# MainBoard.net
KiCad netlist of a schematic drawn in EAGLE
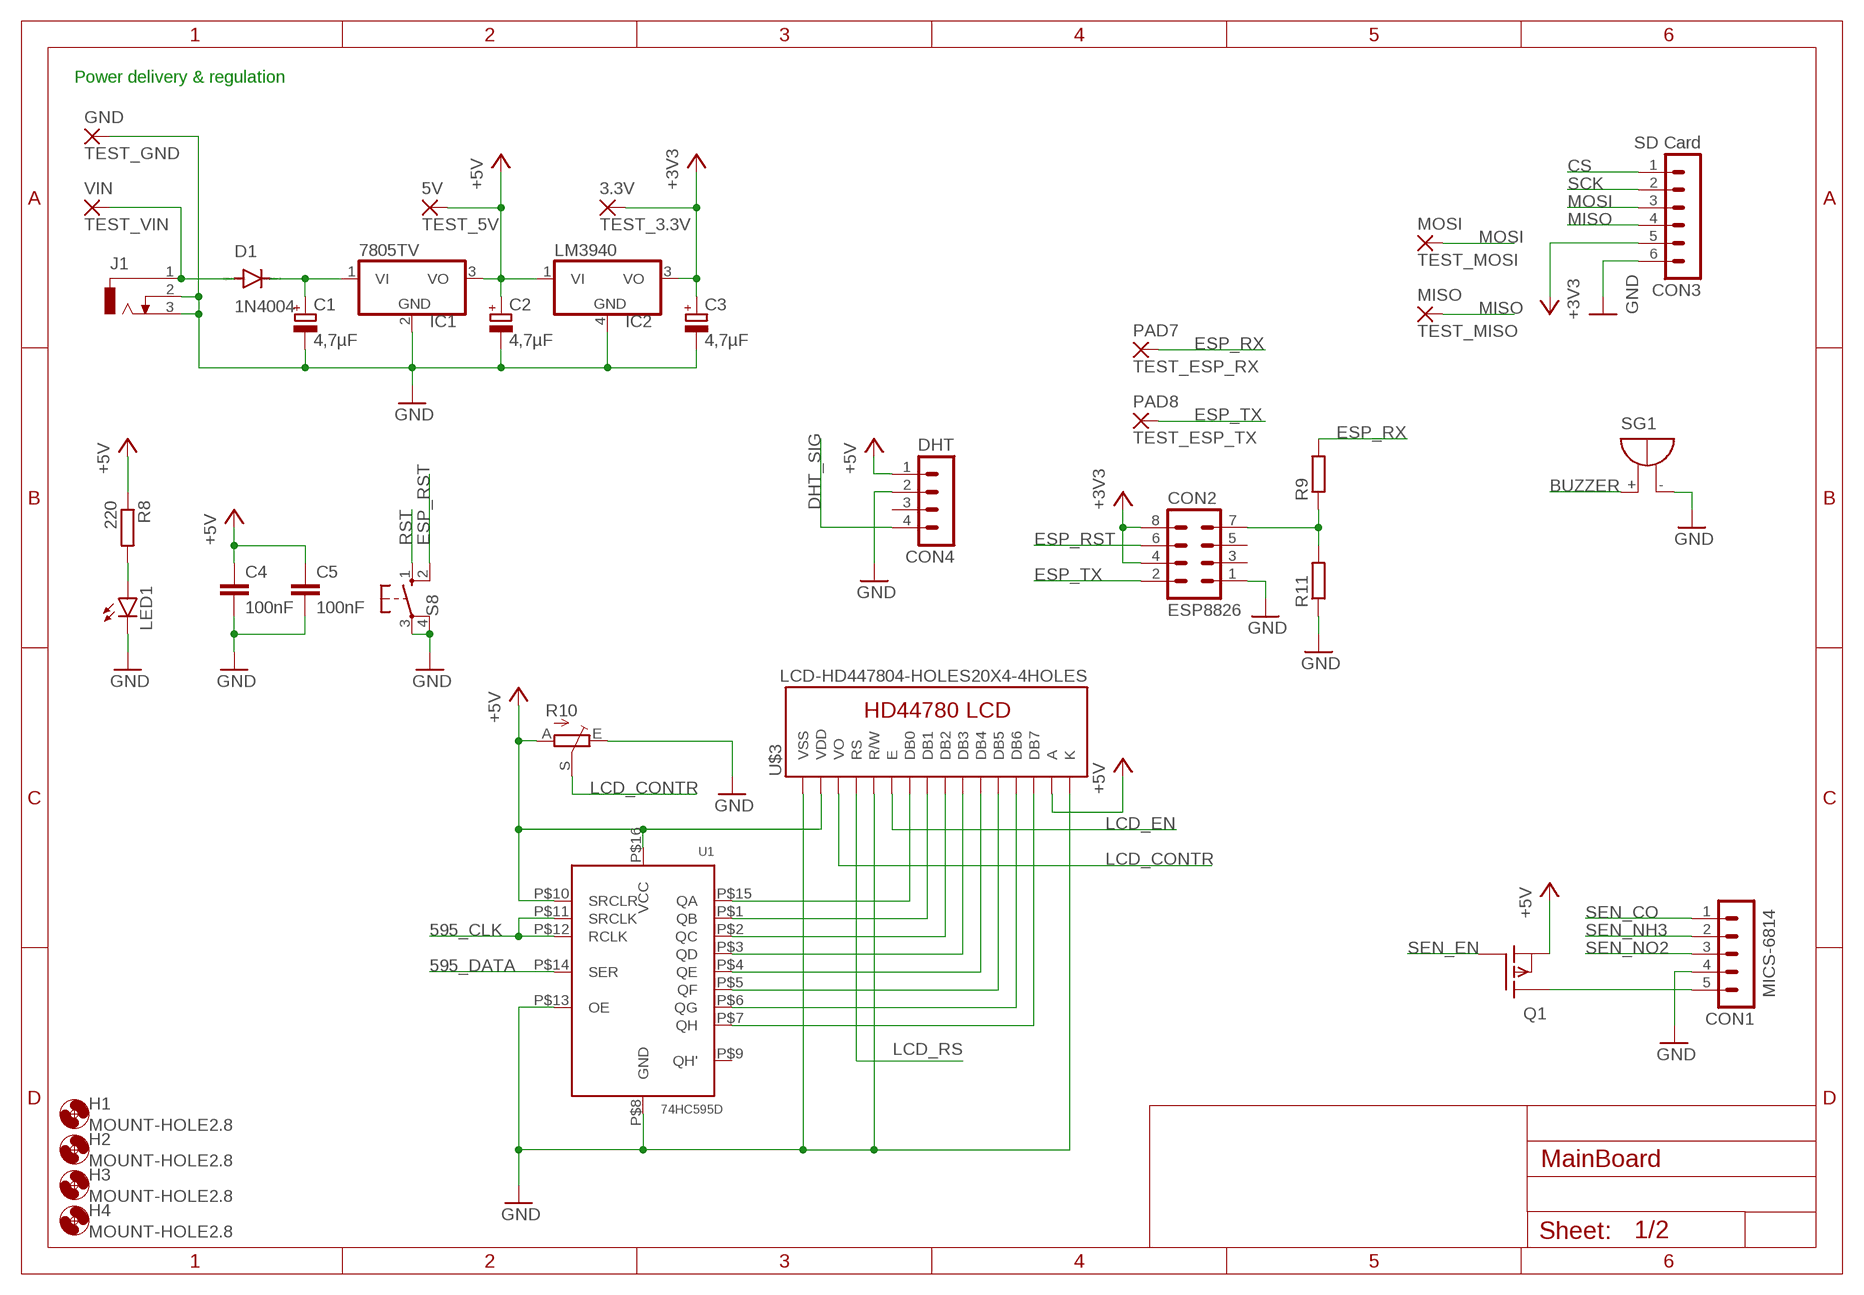
[diagram p0: schematic, sheet 1]
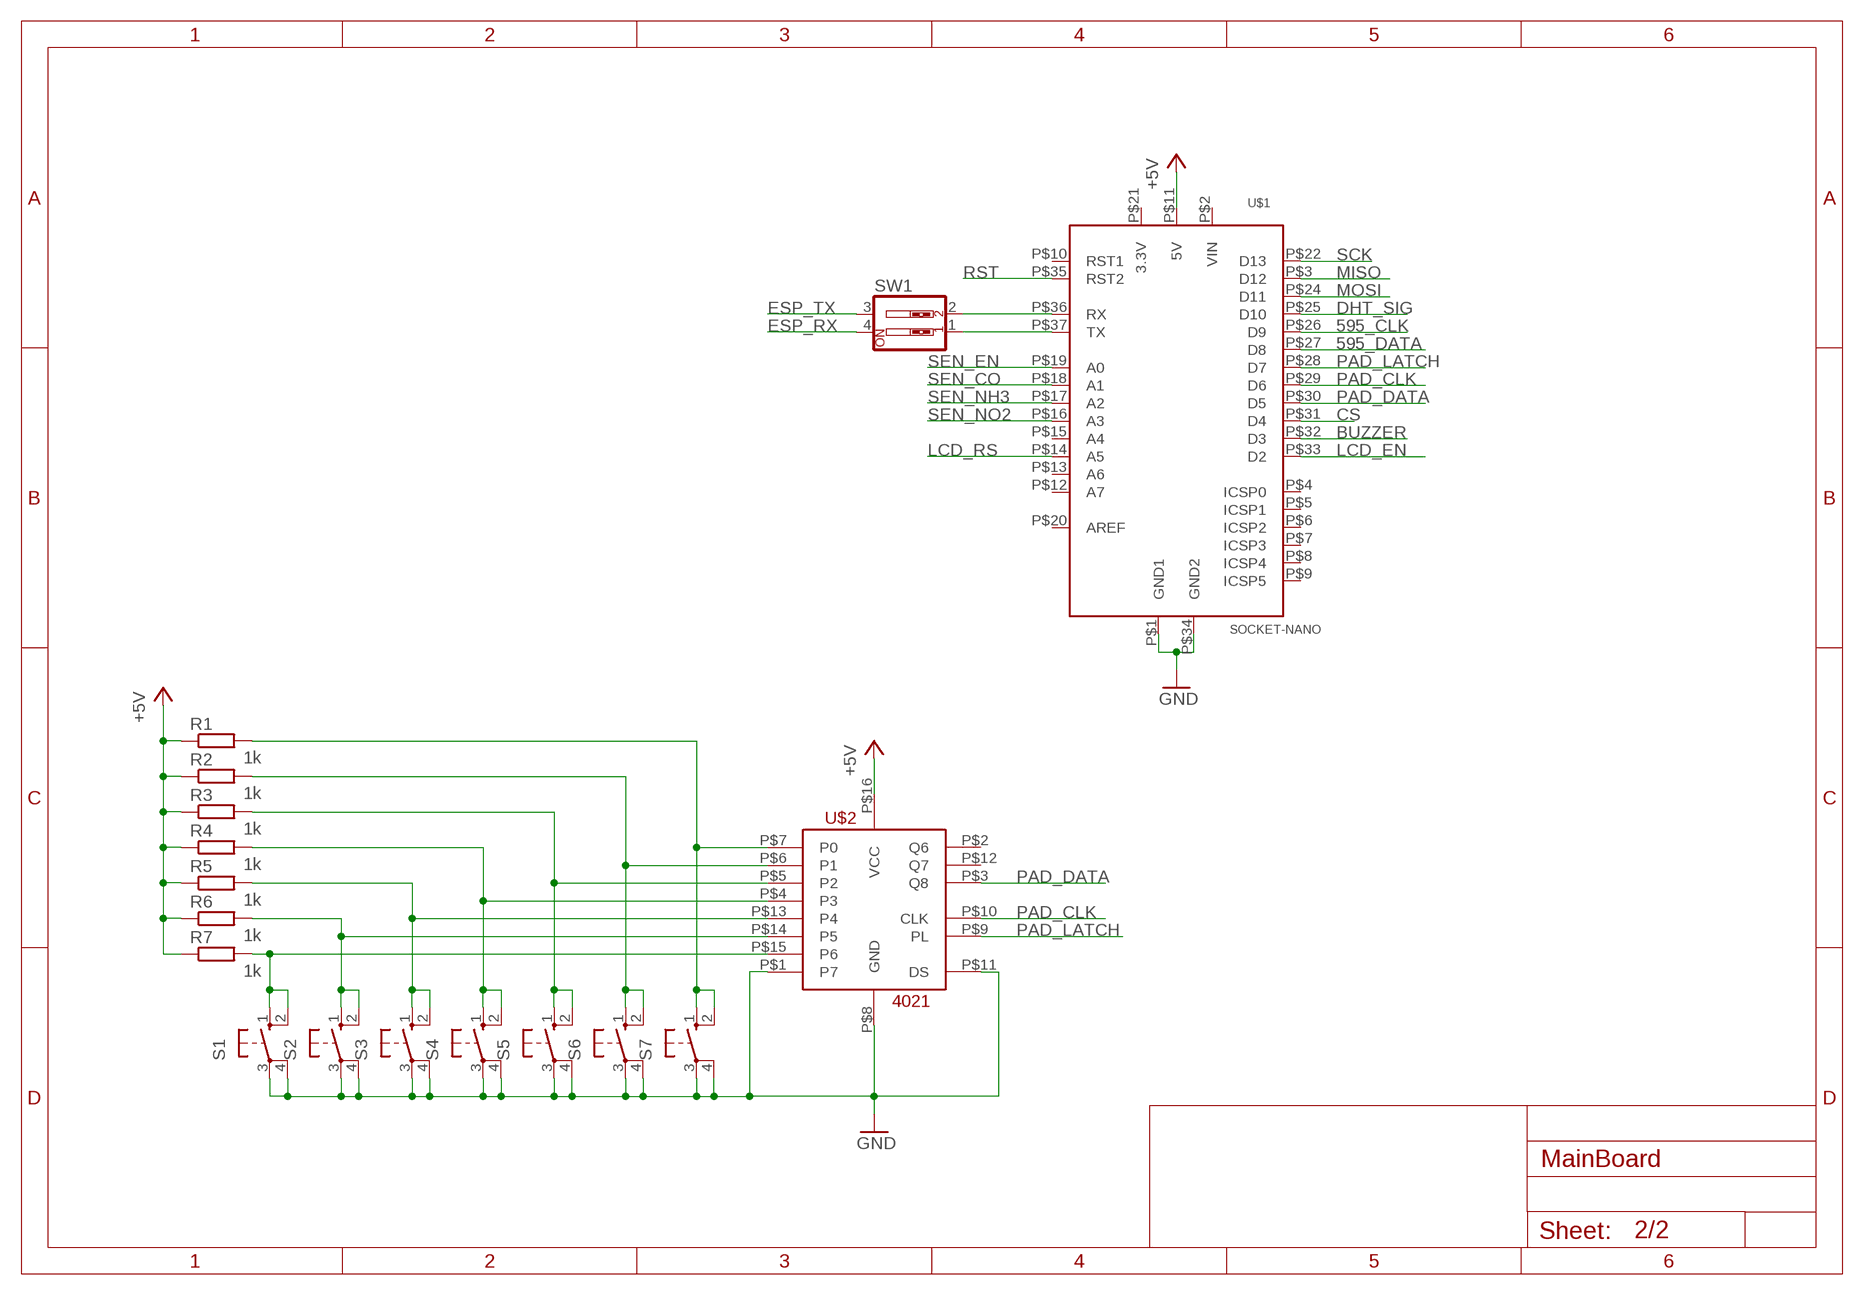
[diagram p1: schematic, sheet 2]

(export (version "E")
  (design (tool "Eeschema 10.0.6"))
  (components
    (comp (ref "3.3V")
      (value "TEST_3.3V")
      (footprint "eagle-import:2,54_0,9")
      (libsource (lib "eagle-import") (part "WIREPAD2,54/0,9"))
    )
    (comp (ref "5V")
      (value "TEST_5V")
      (footprint "eagle-import:2,54_0,9")
      (libsource (lib "eagle-import") (part "WIREPAD2,54/0,9"))
    )
    (comp (ref "C1")
      (value "4,7µF")
      (footprint "eagle-import:E2,5-6E")
      (libsource (lib "eagle-import") (part "CPOL-EUE2,5-6E"))
    )
    (comp (ref "C2")
      (value "4,7µF")
      (footprint "eagle-import:E2,5-6E")
      (libsource (lib "eagle-import") (part "CPOL-EUE2,5-6E"))
    )
    (comp (ref "C3")
      (value "4,7µF")
      (footprint "eagle-import:E2,5-6E")
      (libsource (lib "eagle-import") (part "CPOL-EUE2,5-6E"))
    )
    (comp (ref "C4")
      (value "100nF")
      (footprint "eagle-import:C0805")
      (libsource (lib "eagle-import") (part "C-EUC0805"))
    )
    (comp (ref "C5")
      (value "100nF")
      (footprint "eagle-import:C0805")
      (libsource (lib "eagle-import") (part "C-EUC0805"))
    )
    (comp (ref "CON1")
      (value "MICS-6814")
      (footprint "eagle-import:MA05-1")
      (libsource (lib "eagle-import") (part "MA05-1"))
    )
    (comp (ref "CON2")
      (value "ESP8826")
      (footprint "eagle-import:MA04-2")
      (libsource (lib "eagle-import") (part "MA04-2"))
    )
    (comp (ref "CON3")
      (value "SD Card")
      (footprint "eagle-import:MA06-1")
      (libsource (lib "eagle-import") (part "MA06-1"))
    )
    (comp (ref "CON4")
      (value "DHT")
      (footprint "eagle-import:MA04-1")
      (libsource (lib "eagle-import") (part "MA04-1"))
    )
    (comp (ref "D1")
      (value "1N4004")
      (footprint "eagle-import:DO34-7")
      (libsource (lib "eagle-import") (part "BAS15"))
    )
    (comp (ref "GND")
      (value "TEST_GND")
      (footprint "eagle-import:2,54_0,9")
      (libsource (lib "eagle-import") (part "WIREPAD2,54/0,9"))
    )
    (comp (ref "H1")
      (value "MOUNT-HOLE2.8")
      (footprint "eagle-import:2,8")
      (libsource (lib "eagle-import") (part "MOUNT-HOLE2.8"))
    )
    (comp (ref "H2")
      (value "MOUNT-HOLE2.8")
      (footprint "eagle-import:2,8")
      (libsource (lib "eagle-import") (part "MOUNT-HOLE2.8"))
    )
    (comp (ref "H3")
      (value "MOUNT-HOLE2.8")
      (footprint "eagle-import:2,8")
      (libsource (lib "eagle-import") (part "MOUNT-HOLE2.8"))
    )
    (comp (ref "H4")
      (value "MOUNT-HOLE2.8")
      (footprint "eagle-import:2,8")
      (libsource (lib "eagle-import") (part "MOUNT-HOLE2.8"))
    )
    (comp (ref "IC1")
      (value "7805TV")
      (footprint "eagle-import:TO220V")
      (libsource (lib "eagle-import") (part "78TV05"))
    )
    (comp (ref "IC2")
      (value "LM3940")
      (footprint "eagle-import:SOT223")
      (libsource (lib "eagle-import") (part "LM340?-MP05"))
    )
    (comp (ref "J1")
      (value "DCJ0303")
      (footprint "eagle-import:DCJ0303")
      (libsource (lib "eagle-import") (part "DCJ0303"))
    )
    (comp (ref "LED1")
      (value "LED3MM")
      (footprint "eagle-import:LED3MM")
      (libsource (lib "eagle-import") (part "LED3MM"))
    )
    (comp (ref "MISO")
      (value "TEST_MISO")
      (footprint "eagle-import:2,54_0,9")
      (libsource (lib "eagle-import") (part "WIREPAD2,54/0,9"))
    )
    (comp (ref "MOSI")
      (value "TEST_MOSI")
      (footprint "eagle-import:2,54_0,9")
      (libsource (lib "eagle-import") (part "WIREPAD2,54/0,9"))
    )
    (comp (ref "PAD7")
      (value "TEST_ESP_RX")
      (footprint "eagle-import:2,54_0,9")
      (libsource (lib "eagle-import") (part "WIREPAD2,54/0,9"))
    )
    (comp (ref "PAD8")
      (value "TEST_ESP_TX")
      (footprint "eagle-import:2,54_0,9")
      (libsource (lib "eagle-import") (part "WIREPAD2,54/0,9"))
    )
    (comp (ref "Q1")
      (value "LP0701N3")
      (footprint "eagle-import:TO-92")
      (libsource (lib "eagle-import") (part "LP0701N3"))
    )
    (comp (ref "R8")
      (value "220")
      (footprint "eagle-import:0204_7")
      (libsource (lib "eagle-import") (part "R-EU_0204/7"))
    )
    (comp (ref "R9")
      (value "R-EU_M0805")
      (footprint "eagle-import:M0805")
      (libsource (lib "eagle-import") (part "R-EU_M0805"))
    )
    (comp (ref "R10")
      (value "TRIM_EU-RJ9W")
      (footprint "eagle-import:RJ9W")
      (libsource (lib "eagle-import") (part "TRIM_EU-RJ9W"))
    )
    (comp (ref "R11")
      (value "R-EU_M0805")
      (footprint "eagle-import:M0805")
      (libsource (lib "eagle-import") (part "R-EU_M0805"))
    )
    (comp (ref "S8")
      (value "10-XX")
      (footprint "eagle-import:B3F-10XX")
      (fields (field (name "MPN") "B3F-1000"))
      (libsource (lib "eagle-import") (part "10-XX"))
    )
    (comp (ref "SG1")
      (value "F/TMB")
      (footprint "eagle-import:F_TMB")
      (libsource (lib "eagle-import") (part "F/TMB"))
    )
    (comp (ref "U$3")
      (value "LCD-HD447804-HOLES20X4-4HOLES")
      (footprint "eagle-import:LCD-20X4-4HOLES")
      (libsource (lib "eagle-import") (part "LCD-HD4478020X4-4HOLES4-HOLES"))
    )
    (comp (ref "U1")
      (value "74HC595D")
      (footprint "eagle-import:SOP-16")
      (libsource (lib "eagle-import") (part "74HC595D_SOP16"))
    )
    (comp (ref "VIN")
      (value "TEST_VIN")
      (footprint "eagle-import:2,54_0,9")
      (libsource (lib "eagle-import") (part "WIREPAD2,54/0,9"))
    )
    (comp (ref "R1")
      (value "1k")
      (footprint "eagle-import:0204_7")
      (libsource (lib "eagle-import") (part "R-EU_0204/7"))
    )
    (comp (ref "R2")
      (value "1k")
      (footprint "eagle-import:0204_7")
      (libsource (lib "eagle-import") (part "R-EU_0204/7"))
    )
    (comp (ref "R3")
      (value "1k")
      (footprint "eagle-import:0204_7")
      (libsource (lib "eagle-import") (part "R-EU_0204/7"))
    )
    (comp (ref "R4")
      (value "1k")
      (footprint "eagle-import:0204_7")
      (libsource (lib "eagle-import") (part "R-EU_0204/7"))
    )
    (comp (ref "R5")
      (value "1k")
      (footprint "eagle-import:0204_7")
      (libsource (lib "eagle-import") (part "R-EU_0204/7"))
    )
    (comp (ref "R6")
      (value "1k")
      (footprint "eagle-import:0204_7")
      (libsource (lib "eagle-import") (part "R-EU_0204/7"))
    )
    (comp (ref "R7")
      (value "1k")
      (footprint "eagle-import:0204_7")
      (libsource (lib "eagle-import") (part "R-EU_0204/7"))
    )
    (comp (ref "S1")
      (value "10-XX")
      (footprint "eagle-import:B3F-10XX")
      (fields (field (name "MPN") "B3F-1000"))
      (libsource (lib "eagle-import") (part "10-XX"))
    )
    (comp (ref "S2")
      (value "10-XX")
      (footprint "eagle-import:B3F-10XX")
      (fields (field (name "MPN") "B3F-1000"))
      (libsource (lib "eagle-import") (part "10-XX"))
    )
    (comp (ref "S3")
      (value "10-XX")
      (footprint "eagle-import:B3F-10XX")
      (fields (field (name "MPN") "B3F-1000"))
      (libsource (lib "eagle-import") (part "10-XX"))
    )
    (comp (ref "S4")
      (value "10-XX")
      (footprint "eagle-import:B3F-10XX")
      (fields (field (name "MPN") "B3F-1000"))
      (libsource (lib "eagle-import") (part "10-XX"))
    )
    (comp (ref "S5")
      (value "10-XX")
      (footprint "eagle-import:B3F-10XX")
      (fields (field (name "MPN") "B3F-1000"))
      (libsource (lib "eagle-import") (part "10-XX"))
    )
    (comp (ref "S6")
      (value "10-XX")
      (footprint "eagle-import:B3F-10XX")
      (fields (field (name "MPN") "B3F-1000"))
      (libsource (lib "eagle-import") (part "10-XX"))
    )
    (comp (ref "S7")
      (value "10-XX")
      (footprint "eagle-import:B3F-10XX")
      (fields (field (name "MPN") "B3F-1000"))
      (libsource (lib "eagle-import") (part "10-XX"))
    )
    (comp (ref "SW1")
      (value "SW_DIP-2")
      (footprint "eagle-import:EDG-02")
      (libsource (lib "eagle-import") (part "SW_DIP-2"))
    )
    (comp (ref "U$1")
      (value "SOCKET-NANO")
      (footprint "eagle-import:SOCKET-NANO")
      (libsource (lib "eagle-import") (part "SOCKET-NANO"))
    )
    (comp (ref "U$2")
      (value "4021")
      (footprint "eagle-import:DIP")
      (libsource (lib "eagle-import") (part "4021"))
    )
  )
  (nets
    (net (code "1") (name "+3V3") (class "Default")
      (node (ref "3.3V") (pin "1") (pinfunction "P_1") (pintype "passive"))
      (node (ref "C3") (pin "+") (pinfunction "+_+") (pintype "passive"))
      (node (ref "CON2") (pin "4") (pinfunction "4_4") (pintype "passive"))
      (node (ref "CON2") (pin "8") (pinfunction "8_8") (pintype "passive"))
      (node (ref "CON3") (pin "5") (pinfunction "5_5") (pintype "passive"))
      (node (ref "IC2") (pin "3") (pinfunction "VO_3") (pintype "passive"))
    )
    (net (code "2") (name "+5V") (class "Default")
      (node (ref "5V") (pin "1") (pinfunction "P_1") (pintype "passive"))
      (node (ref "C2") (pin "+") (pinfunction "+_+") (pintype "passive"))
      (node (ref "C4") (pin "1") (pinfunction "1_1") (pintype "passive"))
      (node (ref "C5") (pin "1") (pinfunction "1_1") (pintype "passive"))
      (node (ref "CON4") (pin "1") (pinfunction "1_1") (pintype "passive"))
      (node (ref "IC1") (pin "3") (pinfunction "VO_3") (pintype "passive"))
      (node (ref "IC2") (pin "1") (pinfunction "VI_1") (pintype "input"))
      (node (ref "Q1") (pin "1") (pinfunction "S_1") (pintype "passive"))
      (node (ref "R1") (pin "1") (pinfunction "1_1") (pintype "passive"))
      (node (ref "R10") (pin "A") (pinfunction "A_A") (pintype "passive"))
      (node (ref "R2") (pin "1") (pinfunction "1_1") (pintype "passive"))
      (node (ref "R3") (pin "1") (pinfunction "1_1") (pintype "passive"))
      (node (ref "R4") (pin "1") (pinfunction "1_1") (pintype "passive"))
      (node (ref "R5") (pin "1") (pinfunction "1_1") (pintype "passive"))
      (node (ref "R6") (pin "1") (pinfunction "1_1") (pintype "passive"))
      (node (ref "R7") (pin "1") (pinfunction "1_1") (pintype "passive"))
      (node (ref "R8") (pin "1") (pinfunction "1_1") (pintype "passive"))
      (node (ref "U$1") (pin "P$11") (pinfunction "5V_P$11") (pintype "power_in"))
      (node (ref "U$2") (pin "P$16") (pinfunction "VCC_P$16") (pintype "power_in"))
      (node (ref "U$3") (pin "P$15") (pinfunction "A_P$15") (pintype "power_in"))
      (node (ref "U$3") (pin "P$2") (pinfunction "VDD_P$2") (pintype "power_in"))
      (node (ref "U1") (pin "P$10") (pinfunction "SRCLR_P$10") (pintype "input"))
      (node (ref "U1") (pin "P$16") (pinfunction "VCC_P$16") (pintype "power_in"))
    )
    (net (code "3") (name "3.3V") (class "Default")
      (node (ref "U$1") (pin "P$21") (pinfunction "3.3V_P$21") (pintype "power_in"))
    )
    (net (code "4") (name "595_CLK") (class "Default")
      (node (ref "U$1") (pin "P$26") (pinfunction "D9_P$26") (pintype "bidirectional"))
      (node (ref "U1") (pin "P$11") (pinfunction "SRCLK_P$11") (pintype "input"))
      (node (ref "U1") (pin "P$12") (pinfunction "RCLK_P$12") (pintype "input"))
    )
    (net (code "5") (name "595_DATA") (class "Default")
      (node (ref "U$1") (pin "P$27") (pinfunction "D8_P$27") (pintype "bidirectional"))
      (node (ref "U1") (pin "P$14") (pinfunction "SER_P$14") (pintype "input"))
    )
    (net (code "6") (name "BUZZER") (class "Default")
      (node (ref "SG1") (pin "+") (pinfunction "+_+") (pintype "passive"))
      (node (ref "U$1") (pin "P$32") (pinfunction "D3_P$32") (pintype "bidirectional"))
    )
    (net (code "7") (name "CS") (class "Default")
      (node (ref "CON3") (pin "1") (pinfunction "1_1") (pintype "passive"))
      (node (ref "U$1") (pin "P$31") (pinfunction "D4_P$31") (pintype "bidirectional"))
    )
    (net (code "8") (name "DHT_SIG") (class "Default")
      (node (ref "CON4") (pin "4") (pinfunction "4_4") (pintype "passive"))
      (node (ref "U$1") (pin "P$25") (pinfunction "D10_P$25") (pintype "bidirectional"))
    )
    (net (code "9") (name "ESP_RST") (class "Default")
      (node (ref "CON2") (pin "6") (pinfunction "6_6") (pintype "passive"))
      (node (ref "S8") (pin "2") (pinfunction "S1_2") (pintype "passive"))
    )
    (net (code "10") (name "ESP_RX") (class "Default")
      (node (ref "PAD7") (pin "1") (pinfunction "P_1") (pintype "passive"))
      (node (ref "R9") (pin "2") (pinfunction "2_2") (pintype "passive"))
      (node (ref "SW1") (pin "4") (pinfunction "4_4") (pintype "passive"))
    )
    (net (code "11") (name "ESP_TX") (class "Default")
      (node (ref "CON2") (pin "2") (pinfunction "2_2") (pintype "passive"))
      (node (ref "PAD8") (pin "1") (pinfunction "P_1") (pintype "passive"))
      (node (ref "SW1") (pin "3") (pinfunction "3_3") (pintype "passive"))
    )
    (net (code "12") (name "GND") (class "Default")
      (node (ref "C1") (pin "-") (pinfunction "-_-") (pintype "passive"))
      (node (ref "C2") (pin "-") (pinfunction "-_-") (pintype "passive"))
      (node (ref "C3") (pin "-") (pinfunction "-_-") (pintype "passive"))
      (node (ref "C4") (pin "2") (pinfunction "2_2") (pintype "passive"))
      (node (ref "C5") (pin "2") (pinfunction "2_2") (pintype "passive"))
      (node (ref "CON1") (pin "4") (pinfunction "4_4") (pintype "passive"))
      (node (ref "CON2") (pin "1") (pinfunction "1_1") (pintype "passive"))
      (node (ref "CON3") (pin "6") (pinfunction "6_6") (pintype "passive"))
      (node (ref "CON4") (pin "2") (pinfunction "2_2") (pintype "passive"))
      (node (ref "GND") (pin "1") (pinfunction "P_1") (pintype "passive"))
      (node (ref "IC1") (pin "2") (pinfunction "GND_2") (pintype "passive"))
      (node (ref "IC2") (pin "4") (pinfunction "GND_4") (pintype "passive"))
      (node (ref "J1") (pin "2") (pinfunction "2_2") (pintype "passive"))
      (node (ref "J1") (pin "3") (pinfunction "3_3") (pintype "passive"))
      (node (ref "LED1") (pin "K") (pinfunction "C_K") (pintype "passive"))
      (node (ref "R10") (pin "E") (pinfunction "E_E") (pintype "passive"))
      (node (ref "R11") (pin "1") (pinfunction "1_1") (pintype "passive"))
      (node (ref "S1") (pin "3") (pinfunction "P_3") (pintype "passive"))
      (node (ref "S1") (pin "4") (pinfunction "P1_4") (pintype "passive"))
      (node (ref "S2") (pin "3") (pinfunction "P_3") (pintype "passive"))
      (node (ref "S2") (pin "4") (pinfunction "P1_4") (pintype "passive"))
      (node (ref "S3") (pin "3") (pinfunction "P_3") (pintype "passive"))
      (node (ref "S3") (pin "4") (pinfunction "P1_4") (pintype "passive"))
      (node (ref "S4") (pin "3") (pinfunction "P_3") (pintype "passive"))
      (node (ref "S4") (pin "4") (pinfunction "P1_4") (pintype "passive"))
      (node (ref "S5") (pin "3") (pinfunction "P_3") (pintype "passive"))
      (node (ref "S5") (pin "4") (pinfunction "P1_4") (pintype "passive"))
      (node (ref "S6") (pin "3") (pinfunction "P_3") (pintype "passive"))
      (node (ref "S6") (pin "4") (pinfunction "P1_4") (pintype "passive"))
      (node (ref "S7") (pin "3") (pinfunction "P_3") (pintype "passive"))
      (node (ref "S7") (pin "4") (pinfunction "P1_4") (pintype "passive"))
      (node (ref "S8") (pin "3") (pinfunction "P_3") (pintype "passive"))
      (node (ref "S8") (pin "4") (pinfunction "P1_4") (pintype "passive"))
      (node (ref "SG1") (pin "-") (pinfunction "-_-") (pintype "passive"))
      (node (ref "U$1") (pin "P$1") (pinfunction "GND1_P$1") (pintype "power_in"))
      (node (ref "U$1") (pin "P$34") (pinfunction "GND2_P$34") (pintype "power_in"))
      (node (ref "U$2") (pin "P$1") (pinfunction "P7_P$1") (pintype "input"))
      (node (ref "U$2") (pin "P$11") (pinfunction "DS_P$11") (pintype "bidirectional"))
      (node (ref "U$2") (pin "P$8") (pinfunction "GND_P$8") (pintype "power_in"))
      (node (ref "U$3") (pin "P$1") (pinfunction "VSS_P$1") (pintype "power_in"))
      (node (ref "U$3") (pin "P$16") (pinfunction "K_P$16") (pintype "power_in"))
      (node (ref "U$3") (pin "P$5") (pinfunction "R/W_P$5") (pintype "input"))
      (node (ref "U1") (pin "P$13") (pinfunction "OE_P$13") (pintype "input"))
      (node (ref "U1") (pin "P$8") (pinfunction "GND_P$8") (pintype "power_in"))
    )
    (net (code "13") (name "LCD_CONTR") (class "Default")
      (node (ref "R10") (pin "S") (pinfunction "S_S") (pintype "passive"))
      (node (ref "U$3") (pin "P$3") (pinfunction "VO_P$3") (pintype "bidirectional"))
    )
    (net (code "14") (name "LCD_EN") (class "Default")
      (node (ref "U$1") (pin "P$33") (pinfunction "D2_P$33") (pintype "bidirectional"))
      (node (ref "U$3") (pin "P$6") (pinfunction "E_P$6") (pintype "input"))
    )
    (net (code "15") (name "LCD_RS") (class "Default")
      (node (ref "U$1") (pin "P$14") (pinfunction "A5_P$14") (pintype "bidirectional"))
      (node (ref "U$3") (pin "P$4") (pinfunction "RS_P$4") (pintype "input"))
    )
    (net (code "16") (name "MISO") (class "Default")
      (node (ref "CON3") (pin "4") (pinfunction "4_4") (pintype "passive"))
      (node (ref "MISO") (pin "1") (pinfunction "P_1") (pintype "passive"))
      (node (ref "U$1") (pin "P$3") (pinfunction "D12_P$3") (pintype "bidirectional"))
    )
    (net (code "17") (name "MOSI") (class "Default")
      (node (ref "CON3") (pin "3") (pinfunction "3_3") (pintype "passive"))
      (node (ref "MOSI") (pin "1") (pinfunction "P_1") (pintype "passive"))
      (node (ref "U$1") (pin "P$24") (pinfunction "D11_P$24") (pintype "bidirectional"))
    )
    (net (code "18") (name "Net-(CON2-Pad7)") (class "Default")
      (node (ref "CON2") (pin "7") (pinfunction "7_7") (pintype "passive"))
      (node (ref "R11") (pin "2") (pinfunction "2_2") (pintype "passive"))
      (node (ref "R9") (pin "1") (pinfunction "1_1") (pintype "passive"))
    )
    (net (code "19") (name "Net-(IC1-VI)") (class "Default")
      (node (ref "C1") (pin "+") (pinfunction "+_+") (pintype "passive"))
      (node (ref "D1") (pin "C") (pinfunction "C_C") (pintype "passive"))
      (node (ref "IC1") (pin "1") (pinfunction "VI_1") (pintype "input"))
    )
    (net (code "20") (name "Net-(LED1-PadA)") (class "Default")
      (node (ref "LED1") (pin "A") (pinfunction "A_A") (pintype "passive"))
      (node (ref "R8") (pin "2") (pinfunction "2_2") (pintype "passive"))
    )
    (net (code "21") (name "Net-(Q1-D)") (class "Default")
      (node (ref "CON1") (pin "5") (pinfunction "5_5") (pintype "passive"))
      (node (ref "Q1") (pin "3") (pinfunction "D_3") (pintype "passive"))
    )
    (net (code "22") (name "Net-(S1-S)") (class "Default")
      (node (ref "R7") (pin "2") (pinfunction "2_2") (pintype "passive"))
      (node (ref "S1") (pin "1") (pinfunction "S_1") (pintype "passive"))
      (node (ref "S1") (pin "2") (pinfunction "S1_2") (pintype "passive"))
      (node (ref "U$2") (pin "P$15") (pinfunction "P6_P$15") (pintype "bidirectional"))
    )
    (net (code "23") (name "Net-(S2-S)") (class "Default")
      (node (ref "R6") (pin "2") (pinfunction "2_2") (pintype "passive"))
      (node (ref "S2") (pin "1") (pinfunction "S_1") (pintype "passive"))
      (node (ref "S2") (pin "2") (pinfunction "S1_2") (pintype "passive"))
      (node (ref "U$2") (pin "P$14") (pinfunction "P5_P$14") (pintype "bidirectional"))
    )
    (net (code "24") (name "Net-(S3-S)") (class "Default")
      (node (ref "R5") (pin "2") (pinfunction "2_2") (pintype "passive"))
      (node (ref "S3") (pin "1") (pinfunction "S_1") (pintype "passive"))
      (node (ref "S3") (pin "2") (pinfunction "S1_2") (pintype "passive"))
      (node (ref "U$2") (pin "P$13") (pinfunction "P4_P$13") (pintype "bidirectional"))
    )
    (net (code "25") (name "Net-(S4-S)") (class "Default")
      (node (ref "R4") (pin "2") (pinfunction "2_2") (pintype "passive"))
      (node (ref "S4") (pin "1") (pinfunction "S_1") (pintype "passive"))
      (node (ref "S4") (pin "2") (pinfunction "S1_2") (pintype "passive"))
      (node (ref "U$2") (pin "P$4") (pinfunction "P3_P$4") (pintype "bidirectional"))
    )
    (net (code "26") (name "Net-(S5-S)") (class "Default")
      (node (ref "R3") (pin "2") (pinfunction "2_2") (pintype "passive"))
      (node (ref "S5") (pin "1") (pinfunction "S_1") (pintype "passive"))
      (node (ref "S5") (pin "2") (pinfunction "S1_2") (pintype "passive"))
      (node (ref "U$2") (pin "P$5") (pinfunction "P2_P$5") (pintype "bidirectional"))
    )
    (net (code "27") (name "Net-(S6-S)") (class "Default")
      (node (ref "R2") (pin "2") (pinfunction "2_2") (pintype "passive"))
      (node (ref "S6") (pin "1") (pinfunction "S_1") (pintype "passive"))
      (node (ref "S6") (pin "2") (pinfunction "S1_2") (pintype "passive"))
      (node (ref "U$2") (pin "P$6") (pinfunction "P1_P$6") (pintype "bidirectional"))
    )
    (net (code "28") (name "Net-(S7-S)") (class "Default")
      (node (ref "R1") (pin "2") (pinfunction "2_2") (pintype "passive"))
      (node (ref "S7") (pin "1") (pinfunction "S_1") (pintype "passive"))
      (node (ref "S7") (pin "2") (pinfunction "S1_2") (pintype "passive"))
      (node (ref "U$2") (pin "P$7") (pinfunction "P0_P$7") (pintype "bidirectional"))
    )
    (net (code "29") (name "Net-(U$1-RX)") (class "Default")
      (node (ref "SW1") (pin "2") (pinfunction "2_2") (pintype "passive"))
      (node (ref "U$1") (pin "P$36") (pinfunction "RX_P$36") (pintype "bidirectional"))
    )
    (net (code "30") (name "Net-(U$1-TX)") (class "Default")
      (node (ref "SW1") (pin "1") (pinfunction "1_1") (pintype "passive"))
      (node (ref "U$1") (pin "P$37") (pinfunction "TX_P$37") (pintype "bidirectional"))
    )
    (net (code "31") (name "Net-(U$3-DB0)") (class "Default")
      (node (ref "U$3") (pin "P$7") (pinfunction "DB0_P$7") (pintype "bidirectional"))
      (node (ref "U1") (pin "P$15") (pinfunction "QA_P$15") (pintype "output"))
    )
    (net (code "32") (name "Net-(U$3-DB1)") (class "Default")
      (node (ref "U$3") (pin "P$8") (pinfunction "DB1_P$8") (pintype "bidirectional"))
      (node (ref "U1") (pin "P$1") (pinfunction "QB_P$1") (pintype "output"))
    )
    (net (code "33") (name "Net-(U$3-DB2)") (class "Default")
      (node (ref "U$3") (pin "P$9") (pinfunction "DB2_P$9") (pintype "bidirectional"))
      (node (ref "U1") (pin "P$2") (pinfunction "QC_P$2") (pintype "output"))
    )
    (net (code "34") (name "Net-(U$3-DB3)") (class "Default")
      (node (ref "U$3") (pin "P$10") (pinfunction "DB3_P$10") (pintype "bidirectional"))
      (node (ref "U1") (pin "P$3") (pinfunction "QD_P$3") (pintype "output"))
    )
    (net (code "35") (name "Net-(U$3-DB4)") (class "Default")
      (node (ref "U$3") (pin "P$11") (pinfunction "DB4_P$11") (pintype "bidirectional"))
      (node (ref "U1") (pin "P$4") (pinfunction "QE_P$4") (pintype "output"))
    )
    (net (code "36") (name "Net-(U$3-DB5)") (class "Default")
      (node (ref "U$3") (pin "P$12") (pinfunction "DB5_P$12") (pintype "bidirectional"))
      (node (ref "U1") (pin "P$5") (pinfunction "QF_P$5") (pintype "output"))
    )
    (net (code "37") (name "Net-(U$3-DB6)") (class "Default")
      (node (ref "U$3") (pin "P$13") (pinfunction "DB6_P$13") (pintype "bidirectional"))
      (node (ref "U1") (pin "P$6") (pinfunction "QG_P$6") (pintype "output"))
    )
    (net (code "38") (name "Net-(U$3-DB7)") (class "Default")
      (node (ref "U$3") (pin "P$14") (pinfunction "DB7_P$14") (pintype "bidirectional"))
      (node (ref "U1") (pin "P$7") (pinfunction "QH_P$7") (pintype "output"))
    )
    (net (code "39") (name "Net-(VIN-P)") (class "Default")
      (node (ref "D1") (pin "A") (pinfunction "A_A") (pintype "passive"))
      (node (ref "J1") (pin "1") (pinfunction "1_1") (pintype "passive"))
      (node (ref "VIN") (pin "1") (pinfunction "P_1") (pintype "passive"))
    )
    (net (code "40") (name "PAD_CLK") (class "Default")
      (node (ref "U$1") (pin "P$29") (pinfunction "D6_P$29") (pintype "bidirectional"))
      (node (ref "U$2") (pin "P$10") (pinfunction "CLK_P$10") (pintype "bidirectional"))
    )
    (net (code "41") (name "PAD_DATA") (class "Default")
      (node (ref "U$1") (pin "P$30") (pinfunction "D5_P$30") (pintype "bidirectional"))
      (node (ref "U$2") (pin "P$3") (pinfunction "Q8_P$3") (pintype "bidirectional"))
    )
    (net (code "42") (name "PAD_LATCH") (class "Default")
      (node (ref "U$1") (pin "P$28") (pinfunction "D7_P$28") (pintype "bidirectional"))
      (node (ref "U$2") (pin "P$9") (pinfunction "PL_P$9") (pintype "bidirectional"))
    )
    (net (code "43") (name "RST") (class "Default")
      (node (ref "S8") (pin "1") (pinfunction "S_1") (pintype "passive"))
      (node (ref "U$1") (pin "P$35") (pinfunction "RST2_P$35") (pintype "bidirectional"))
    )
    (net (code "44") (name "SCK") (class "Default")
      (node (ref "CON3") (pin "2") (pinfunction "2_2") (pintype "passive"))
      (node (ref "U$1") (pin "P$22") (pinfunction "D13_P$22") (pintype "bidirectional"))
    )
    (net (code "45") (name "SEN_CO") (class "Default")
      (node (ref "CON1") (pin "1") (pinfunction "1_1") (pintype "passive"))
      (node (ref "U$1") (pin "P$18") (pinfunction "A1_P$18") (pintype "bidirectional"))
    )
    (net (code "46") (name "SEN_EN") (class "Default")
      (node (ref "Q1") (pin "2") (pinfunction "G_2") (pintype "passive"))
      (node (ref "U$1") (pin "P$19") (pinfunction "A0_P$19") (pintype "bidirectional"))
    )
    (net (code "47") (name "SEN_NH3") (class "Default")
      (node (ref "CON1") (pin "2") (pinfunction "2_2") (pintype "passive"))
      (node (ref "U$1") (pin "P$17") (pinfunction "A2_P$17") (pintype "bidirectional"))
    )
    (net (code "48") (name "SEN_NO2") (class "Default")
      (node (ref "CON1") (pin "3") (pinfunction "3_3") (pintype "passive"))
      (node (ref "U$1") (pin "P$16") (pinfunction "A3_P$16") (pintype "bidirectional"))
    )
    (net (code "49") (name "VIN") (class "Default")
      (node (ref "U$1") (pin "P$2") (pinfunction "VIN_P$2") (pintype "power_in"))
    )
    (net (code "50") (name "unconnected-(CON2-Pad3)") (class "Default")
      (node (ref "CON2") (pin "3") (pinfunction "3_3") (pintype "passive"))
    )
    (net (code "51") (name "unconnected-(CON2-Pad5)") (class "Default")
      (node (ref "CON2") (pin "5") (pinfunction "5_5") (pintype "passive"))
    )
    (net (code "52") (name "unconnected-(CON4-Pad3)") (class "Default")
      (node (ref "CON4") (pin "3") (pinfunction "3_3") (pintype "passive"))
    )
    (net (code "53") (name "unconnected-(U$1-A4-PadP$15)") (class "Default")
      (node (ref "U$1") (pin "P$15") (pinfunction "A4_P$15") (pintype "bidirectional"))
    )
    (net (code "54") (name "unconnected-(U$1-A6-PadP$13)") (class "Default")
      (node (ref "U$1") (pin "P$13") (pinfunction "A6_P$13") (pintype "bidirectional"))
    )
    (net (code "55") (name "unconnected-(U$1-A7-PadP$12)") (class "Default")
      (node (ref "U$1") (pin "P$12") (pinfunction "A7_P$12") (pintype "bidirectional"))
    )
    (net (code "56") (name "unconnected-(U$1-AREF-PadP$20)") (class "Default")
      (node (ref "U$1") (pin "P$20") (pinfunction "AREF_P$20") (pintype "bidirectional"))
    )
    (net (code "57") (name "unconnected-(U$1-ICSP0-PadP$4)") (class "Default")
      (node (ref "U$1") (pin "P$4") (pinfunction "ICSP0_P$4") (pintype "bidirectional"))
    )
    (net (code "58") (name "unconnected-(U$1-ICSP1-PadP$5)") (class "Default")
      (node (ref "U$1") (pin "P$5") (pinfunction "ICSP1_P$5") (pintype "bidirectional"))
    )
    (net (code "59") (name "unconnected-(U$1-ICSP2-PadP$6)") (class "Default")
      (node (ref "U$1") (pin "P$6") (pinfunction "ICSP2_P$6") (pintype "bidirectional"))
    )
    (net (code "60") (name "unconnected-(U$1-ICSP3-PadP$7)") (class "Default")
      (node (ref "U$1") (pin "P$7") (pinfunction "ICSP3_P$7") (pintype "bidirectional"))
    )
    (net (code "61") (name "unconnected-(U$1-ICSP4-PadP$8)") (class "Default")
      (node (ref "U$1") (pin "P$8") (pinfunction "ICSP4_P$8") (pintype "bidirectional"))
    )
    (net (code "62") (name "unconnected-(U$1-ICSP5-PadP$9)") (class "Default")
      (node (ref "U$1") (pin "P$9") (pinfunction "ICSP5_P$9") (pintype "bidirectional"))
    )
    (net (code "63") (name "unconnected-(U$1-RST1-PadP$10)") (class "Default")
      (node (ref "U$1") (pin "P$10") (pinfunction "RST1_P$10") (pintype "bidirectional"))
    )
    (net (code "64") (name "unconnected-(U$2-Q6-PadP$2)") (class "Default")
      (node (ref "U$2") (pin "P$2") (pinfunction "Q6_P$2") (pintype "bidirectional"))
    )
    (net (code "65") (name "unconnected-(U$2-Q7-PadP$12)") (class "Default")
      (node (ref "U$2") (pin "P$12") (pinfunction "Q7_P$12") (pintype "bidirectional"))
    )
    (net (code "66") (name "unconnected-(U1-QH'-PadP$9)") (class "Default")
      (node (ref "U1") (pin "P$9") (pinfunction "QH'_P$9") (pintype "output"))
    )
  )
)
